# svf1.net
KiCad netlist of a schematic drawn in EAGLE
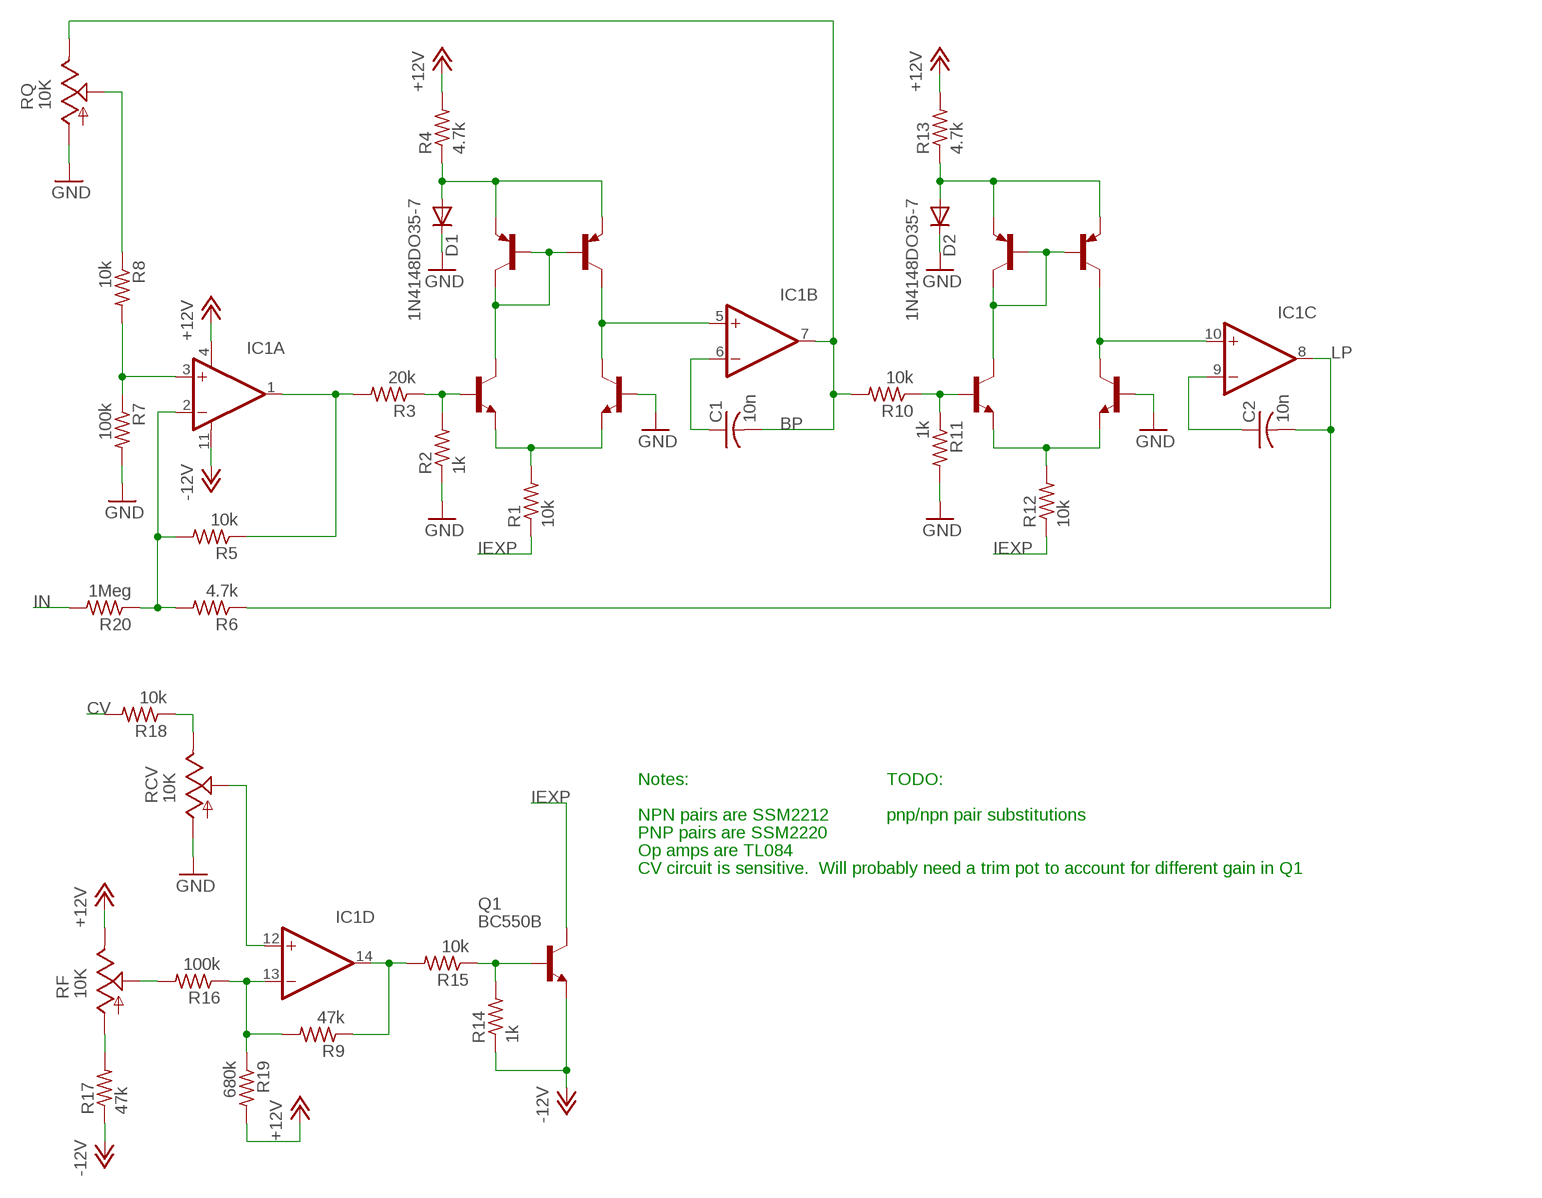
[diagram p0: schematic, sheet 1]

(export (version "E")
  (design (tool "Eeschema 10.0.6"))
  (components
    (comp (ref "C1")
      (value "10n")
      (footprint "eagle-import:C075-032X103")
      (libsource (lib "eagle-import") (part "C-US075-032X103"))
    )
    (comp (ref "C2")
      (value "10n")
      (footprint "eagle-import:C075-032X103")
      (libsource (lib "eagle-import") (part "C-US075-032X103"))
    )
    (comp (ref "D1")
      (value "1N4148DO35-7")
      (footprint "eagle-import:DO35-7")
      (libsource (lib "eagle-import") (part "1N4148DO35-7"))
    )
    (comp (ref "D2")
      (value "1N4148DO35-7")
      (footprint "eagle-import:DO35-7")
      (libsource (lib "eagle-import") (part "1N4148DO35-7"))
    )
    (comp (ref "IC1")
      (value "OPA4130P")
      (footprint "eagle-import:DIL14")
      (libsource (lib "eagle-import") (part "OPA4130P"))
    )
    (comp (ref "Q1")
      (value "BC550B")
      (footprint "eagle-import:TO92-EBC")
      (libsource (lib "eagle-import") (part "BC550B"))
    )
    (comp (ref "R1")
      (value "10k")
      (footprint "eagle-import:0207_2V")
      (libsource (lib "eagle-import") (part "R-US_0207/2V"))
    )
    (comp (ref "R2")
      (value "1k")
      (footprint "eagle-import:0207_2V")
      (libsource (lib "eagle-import") (part "R-US_0207/2V"))
    )
    (comp (ref "R3")
      (value "20k")
      (footprint "eagle-import:0207_2V")
      (libsource (lib "eagle-import") (part "R-US_0207/2V"))
    )
    (comp (ref "R4")
      (value "4.7k")
      (footprint "eagle-import:0207_2V")
      (libsource (lib "eagle-import") (part "R-US_0207/2V"))
    )
    (comp (ref "R5")
      (value "10k")
      (footprint "eagle-import:0207_2V")
      (libsource (lib "eagle-import") (part "R-US_0207/2V"))
    )
    (comp (ref "R6")
      (value "4.7k")
      (footprint "eagle-import:0207_2V")
      (libsource (lib "eagle-import") (part "R-US_0207/2V"))
    )
    (comp (ref "R7")
      (value "100k")
      (footprint "eagle-import:0207_2V")
      (libsource (lib "eagle-import") (part "R-US_0207/2V"))
    )
    (comp (ref "R8")
      (value "10k")
      (footprint "eagle-import:0207_2V")
      (libsource (lib "eagle-import") (part "R-US_0207/2V"))
    )
    (comp (ref "R9")
      (value "47k")
      (footprint "eagle-import:0207_2V")
      (libsource (lib "eagle-import") (part "R-US_0207/2V"))
    )
    (comp (ref "R10")
      (value "10k")
      (footprint "eagle-import:0207_2V")
      (libsource (lib "eagle-import") (part "R-US_0207/2V"))
    )
    (comp (ref "R11")
      (value "1k")
      (footprint "eagle-import:0207_2V")
      (libsource (lib "eagle-import") (part "R-US_0207/2V"))
    )
    (comp (ref "R12")
      (value "10k")
      (footprint "eagle-import:0207_2V")
      (libsource (lib "eagle-import") (part "R-US_0207/2V"))
    )
    (comp (ref "R13")
      (value "4.7k")
      (footprint "eagle-import:0207_2V")
      (libsource (lib "eagle-import") (part "R-US_0207/2V"))
    )
    (comp (ref "R14")
      (value "1k")
      (footprint "eagle-import:0207_2V")
      (libsource (lib "eagle-import") (part "R-US_0207/2V"))
    )
    (comp (ref "R15")
      (value "10k")
      (footprint "eagle-import:0207_2V")
      (libsource (lib "eagle-import") (part "R-US_0207/2V"))
    )
    (comp (ref "R16")
      (value "100k")
      (footprint "eagle-import:0207_2V")
      (libsource (lib "eagle-import") (part "R-US_0207/2V"))
    )
    (comp (ref "R17")
      (value "47k")
      (footprint "eagle-import:0207_2V")
      (libsource (lib "eagle-import") (part "R-US_0207/2V"))
    )
    (comp (ref "R18")
      (value "10k")
      (footprint "eagle-import:0207_2V")
      (libsource (lib "eagle-import") (part "R-US_0207/2V"))
    )
    (comp (ref "R19")
      (value "680k")
      (footprint "eagle-import:0207_2V")
      (libsource (lib "eagle-import") (part "R-US_0207/2V"))
    )
    (comp (ref "R20")
      (value "1Meg")
      (footprint "eagle-import:0207_2V")
      (libsource (lib "eagle-import") (part "R-US_0207/2V"))
    )
    (comp (ref "RCV")
      (value "10K")
      (footprint "eagle-import:EVUFXJ")
      (libsource (lib "eagle-import") (part "US-EVUF3J"))
    )
    (comp (ref "RF")
      (value "10K")
      (footprint "eagle-import:EVUFXJ")
      (libsource (lib "eagle-import") (part "US-EVUF3J"))
    )
    (comp (ref "RQ")
      (value "10K")
      (footprint "eagle-import:EVUFXJ")
      (libsource (lib "eagle-import") (part "US-EVUF3J"))
    )
    (comp (ref "U$1")
      (value "BCM847")
      (footprint "eagle-import:SOT457R_PHILIPS")
      (libsource (lib "eagle-import") (part "BCM847"))
    )
    (comp (ref "U$2")
      (value "BCM857")
      (footprint "eagle-import:SOT457R_PHILIPS")
      (libsource (lib "eagle-import") (part "BCM857"))
    )
    (comp (ref "U$4")
      (value "BCM847")
      (footprint "eagle-import:SOT457R_PHILIPS")
      (libsource (lib "eagle-import") (part "BCM847"))
    )
    (comp (ref "U$5")
      (value "BCM857")
      (footprint "eagle-import:SOT457R_PHILIPS")
      (libsource (lib "eagle-import") (part "BCM857"))
    )
  )
  (nets
    (net (code "1") (name "+12V") (class "Default")
      (node (ref "IC1") (pin "4") (pinfunction "V+_4") (pintype "power_in"))
      (node (ref "R13") (pin "2") (pinfunction "2_2") (pintype "passive"))
      (node (ref "R19") (pin "2") (pinfunction "2_2") (pintype "passive"))
      (node (ref "R4") (pin "2") (pinfunction "2_2") (pintype "passive"))
      (node (ref "RF") (pin "3") (pinfunction "E_3") (pintype "passive"))
    )
    (net (code "2") (name "-12V") (class "Default")
      (node (ref "IC1") (pin "11") (pinfunction "V-_11") (pintype "power_in"))
      (node (ref "Q1") (pin "E") (pinfunction "E_E") (pintype "passive"))
      (node (ref "R14") (pin "1") (pinfunction "1_1") (pintype "passive"))
      (node (ref "R17") (pin "1") (pinfunction "1_1") (pintype "passive"))
    )
    (net (code "3") (name "/BP") (class "Default")
      (node (ref "C1") (pin "2") (pinfunction "2_2") (pintype "passive"))
      (node (ref "IC1") (pin "7") (pinfunction "OUT_7") (pintype "output"))
      (node (ref "R10") (pin "2") (pinfunction "2_2") (pintype "passive"))
      (node (ref "RQ") (pin "3") (pinfunction "E_3") (pintype "passive"))
    )
    (net (code "4") (name "/CV") (class "Default")
      (node (ref "R18") (pin "1") (pinfunction "1_1") (pintype "passive"))
      (node (ref "RCV") (pin "3") (pinfunction "E_3") (pintype "passive"))
    )
    (net (code "5") (name "/IEXP") (class "Default")
      (node (ref "Q1") (pin "C") (pinfunction "C_C") (pintype "passive"))
      (node (ref "R1") (pin "1") (pinfunction "1_1") (pintype "passive"))
      (node (ref "R12") (pin "1") (pinfunction "1_1") (pintype "passive"))
    )
    (net (code "6") (name "/IN") (class "Default")
      (node (ref "R20") (pin "2") (pinfunction "2_2") (pintype "passive"))
    )
    (net (code "7") (name "/LP") (class "Default")
      (node (ref "C2") (pin "2") (pinfunction "2_2") (pintype "passive"))
      (node (ref "IC1") (pin "8") (pinfunction "OUT_8") (pintype "output"))
      (node (ref "R6") (pin "1") (pinfunction "1_1") (pintype "passive"))
    )
    (net (code "8") (name "GND") (class "Default")
      (node (ref "D1") (pin "C") (pinfunction "C_C") (pintype "passive"))
      (node (ref "D2") (pin "C") (pinfunction "C_C") (pintype "passive"))
      (node (ref "R11") (pin "2") (pinfunction "2_2") (pintype "passive"))
      (node (ref "R2") (pin "1") (pinfunction "1_1") (pintype "passive"))
      (node (ref "R7") (pin "2") (pinfunction "2_2") (pintype "passive"))
      (node (ref "RCV") (pin "1") (pinfunction "A_1") (pintype "passive"))
      (node (ref "RQ") (pin "1") (pinfunction "A_1") (pintype "passive"))
      (node (ref "U$1") (pin "5") (pinfunction "B_5") (pintype "passive"))
      (node (ref "U$4") (pin "5") (pinfunction "B_5") (pintype "passive"))
    )
    (net (code "9") (name "Net-(IC1A-+IN)") (class "Default")
      (node (ref "IC1") (pin "3") (pinfunction "+IN_3") (pintype "input"))
      (node (ref "R7") (pin "1") (pinfunction "1_1") (pintype "passive"))
      (node (ref "R8") (pin "2") (pinfunction "2_2") (pintype "passive"))
    )
    (net (code "10") (name "Net-(IC1A--IN)") (class "Default")
      (node (ref "IC1") (pin "2") (pinfunction "-IN_2") (pintype "input"))
      (node (ref "R20") (pin "1") (pinfunction "1_1") (pintype "passive"))
      (node (ref "R5") (pin "2") (pinfunction "2_2") (pintype "passive"))
      (node (ref "R6") (pin "2") (pinfunction "2_2") (pintype "passive"))
    )
    (net (code "11") (name "Net-(IC1A-OUT)") (class "Default")
      (node (ref "IC1") (pin "1") (pinfunction "OUT_1") (pintype "output"))
      (node (ref "R3") (pin "2") (pinfunction "2_2") (pintype "passive"))
      (node (ref "R5") (pin "1") (pinfunction "1_1") (pintype "passive"))
    )
    (net (code "12") (name "Net-(IC1B-+IN)") (class "Default")
      (node (ref "IC1") (pin "5") (pinfunction "+IN_5") (pintype "input"))
      (node (ref "U$1") (pin "3") (pinfunction "C_3") (pintype "passive"))
      (node (ref "U$2") (pin "3") (pinfunction "C_3") (pintype "passive"))
    )
    (net (code "13") (name "Net-(IC1B--IN)") (class "Default")
      (node (ref "C1") (pin "1") (pinfunction "1_1") (pintype "passive"))
      (node (ref "IC1") (pin "6") (pinfunction "-IN_6") (pintype "input"))
    )
    (net (code "14") (name "Net-(IC1C-+IN)") (class "Default")
      (node (ref "IC1") (pin "10") (pinfunction "+IN_10") (pintype "input"))
      (node (ref "U$4") (pin "3") (pinfunction "C_3") (pintype "passive"))
      (node (ref "U$5") (pin "3") (pinfunction "C_3") (pintype "passive"))
    )
    (net (code "15") (name "Net-(IC1C--IN)") (class "Default")
      (node (ref "C2") (pin "1") (pinfunction "1_1") (pintype "passive"))
      (node (ref "IC1") (pin "9") (pinfunction "-IN_9") (pintype "input"))
    )
    (net (code "16") (name "Net-(IC1D-+IN)") (class "Default")
      (node (ref "IC1") (pin "12") (pinfunction "+IN_12") (pintype "input"))
      (node (ref "RCV") (pin "2") (pinfunction "S_2") (pintype "passive"))
    )
    (net (code "17") (name "Net-(IC1D--IN)") (class "Default")
      (node (ref "IC1") (pin "13") (pinfunction "-IN_13") (pintype "input"))
      (node (ref "R16") (pin "1") (pinfunction "1_1") (pintype "passive"))
      (node (ref "R19") (pin "1") (pinfunction "1_1") (pintype "passive"))
      (node (ref "R9") (pin "2") (pinfunction "2_2") (pintype "passive"))
    )
    (net (code "18") (name "Net-(IC1D-OUT)") (class "Default")
      (node (ref "IC1") (pin "14") (pinfunction "OUT_14") (pintype "output"))
      (node (ref "R15") (pin "2") (pinfunction "2_2") (pintype "passive"))
      (node (ref "R9") (pin "1") (pinfunction "1_1") (pintype "passive"))
    )
    (net (code "19") (name "Net-(Q1-PadB)") (class "Default")
      (node (ref "Q1") (pin "B") (pinfunction "B_B") (pintype "passive"))
      (node (ref "R14") (pin "2") (pinfunction "2_2") (pintype "passive"))
      (node (ref "R15") (pin "1") (pinfunction "1_1") (pintype "passive"))
    )
    (net (code "20") (name "Net-(RF-A)") (class "Default")
      (node (ref "R17") (pin "2") (pinfunction "2_2") (pintype "passive"))
      (node (ref "RF") (pin "1") (pinfunction "A_1") (pintype "passive"))
    )
    (net (code "21") (name "Net-(RF-S)") (class "Default")
      (node (ref "R16") (pin "2") (pinfunction "2_2") (pintype "passive"))
      (node (ref "RF") (pin "2") (pinfunction "S_2") (pintype "passive"))
    )
    (net (code "22") (name "Net-(RQ-S)") (class "Default")
      (node (ref "R8") (pin "1") (pinfunction "1_1") (pintype "passive"))
      (node (ref "RQ") (pin "2") (pinfunction "S_2") (pintype "passive"))
    )
    (net (code "23") (name "Net-(U$1A-B)") (class "Default")
      (node (ref "R2") (pin "2") (pinfunction "2_2") (pintype "passive"))
      (node (ref "R3") (pin "1") (pinfunction "1_1") (pintype "passive"))
      (node (ref "U$1") (pin "2") (pinfunction "B_2") (pintype "passive"))
    )
    (net (code "24") (name "Net-(U$1A-C)") (class "Default")
      (node (ref "U$1") (pin "6") (pinfunction "C_6") (pintype "passive"))
      (node (ref "U$2") (pin "2") (pinfunction "B_2") (pintype "passive"))
      (node (ref "U$2") (pin "5") (pinfunction "B_5") (pintype "passive"))
      (node (ref "U$2") (pin "6") (pinfunction "C_6") (pintype "passive"))
    )
    (net (code "25") (name "Net-(U$1A-E)") (class "Default")
      (node (ref "R1") (pin "2") (pinfunction "2_2") (pintype "passive"))
      (node (ref "U$1") (pin "1") (pinfunction "E_1") (pintype "passive"))
      (node (ref "U$1") (pin "4") (pinfunction "E_4") (pintype "passive"))
    )
    (net (code "26") (name "Net-(U$2A-E)") (class "Default")
      (node (ref "D1") (pin "A") (pinfunction "A_A") (pintype "passive"))
      (node (ref "R4") (pin "1") (pinfunction "1_1") (pintype "passive"))
      (node (ref "U$2") (pin "1") (pinfunction "E_1") (pintype "passive"))
      (node (ref "U$2") (pin "4") (pinfunction "E_4") (pintype "passive"))
    )
    (net (code "27") (name "Net-(U$4A-B)") (class "Default")
      (node (ref "R10") (pin "1") (pinfunction "1_1") (pintype "passive"))
      (node (ref "R11") (pin "1") (pinfunction "1_1") (pintype "passive"))
      (node (ref "U$4") (pin "2") (pinfunction "B_2") (pintype "passive"))
    )
    (net (code "28") (name "Net-(U$4A-C)") (class "Default")
      (node (ref "U$4") (pin "6") (pinfunction "C_6") (pintype "passive"))
      (node (ref "U$5") (pin "2") (pinfunction "B_2") (pintype "passive"))
      (node (ref "U$5") (pin "5") (pinfunction "B_5") (pintype "passive"))
      (node (ref "U$5") (pin "6") (pinfunction "C_6") (pintype "passive"))
    )
    (net (code "29") (name "Net-(U$4A-E)") (class "Default")
      (node (ref "R12") (pin "2") (pinfunction "2_2") (pintype "passive"))
      (node (ref "U$4") (pin "1") (pinfunction "E_1") (pintype "passive"))
      (node (ref "U$4") (pin "4") (pinfunction "E_4") (pintype "passive"))
    )
    (net (code "30") (name "Net-(U$5A-E)") (class "Default")
      (node (ref "D2") (pin "A") (pinfunction "A_A") (pintype "passive"))
      (node (ref "R13") (pin "1") (pinfunction "1_1") (pintype "passive"))
      (node (ref "U$5") (pin "1") (pinfunction "E_1") (pintype "passive"))
      (node (ref "U$5") (pin "4") (pinfunction "E_4") (pintype "passive"))
    )
    (net (code "31") (name "unconnected-(R18-Pad2)") (class "Default")
      (node (ref "R18") (pin "2") (pinfunction "2_2") (pintype "passive"))
    )
  )
)
